# SCH_Sensor_Universal_PCB_w_XOR_2023-07-0.net
KiCad netlist of a schematic drawn in EasyEDA
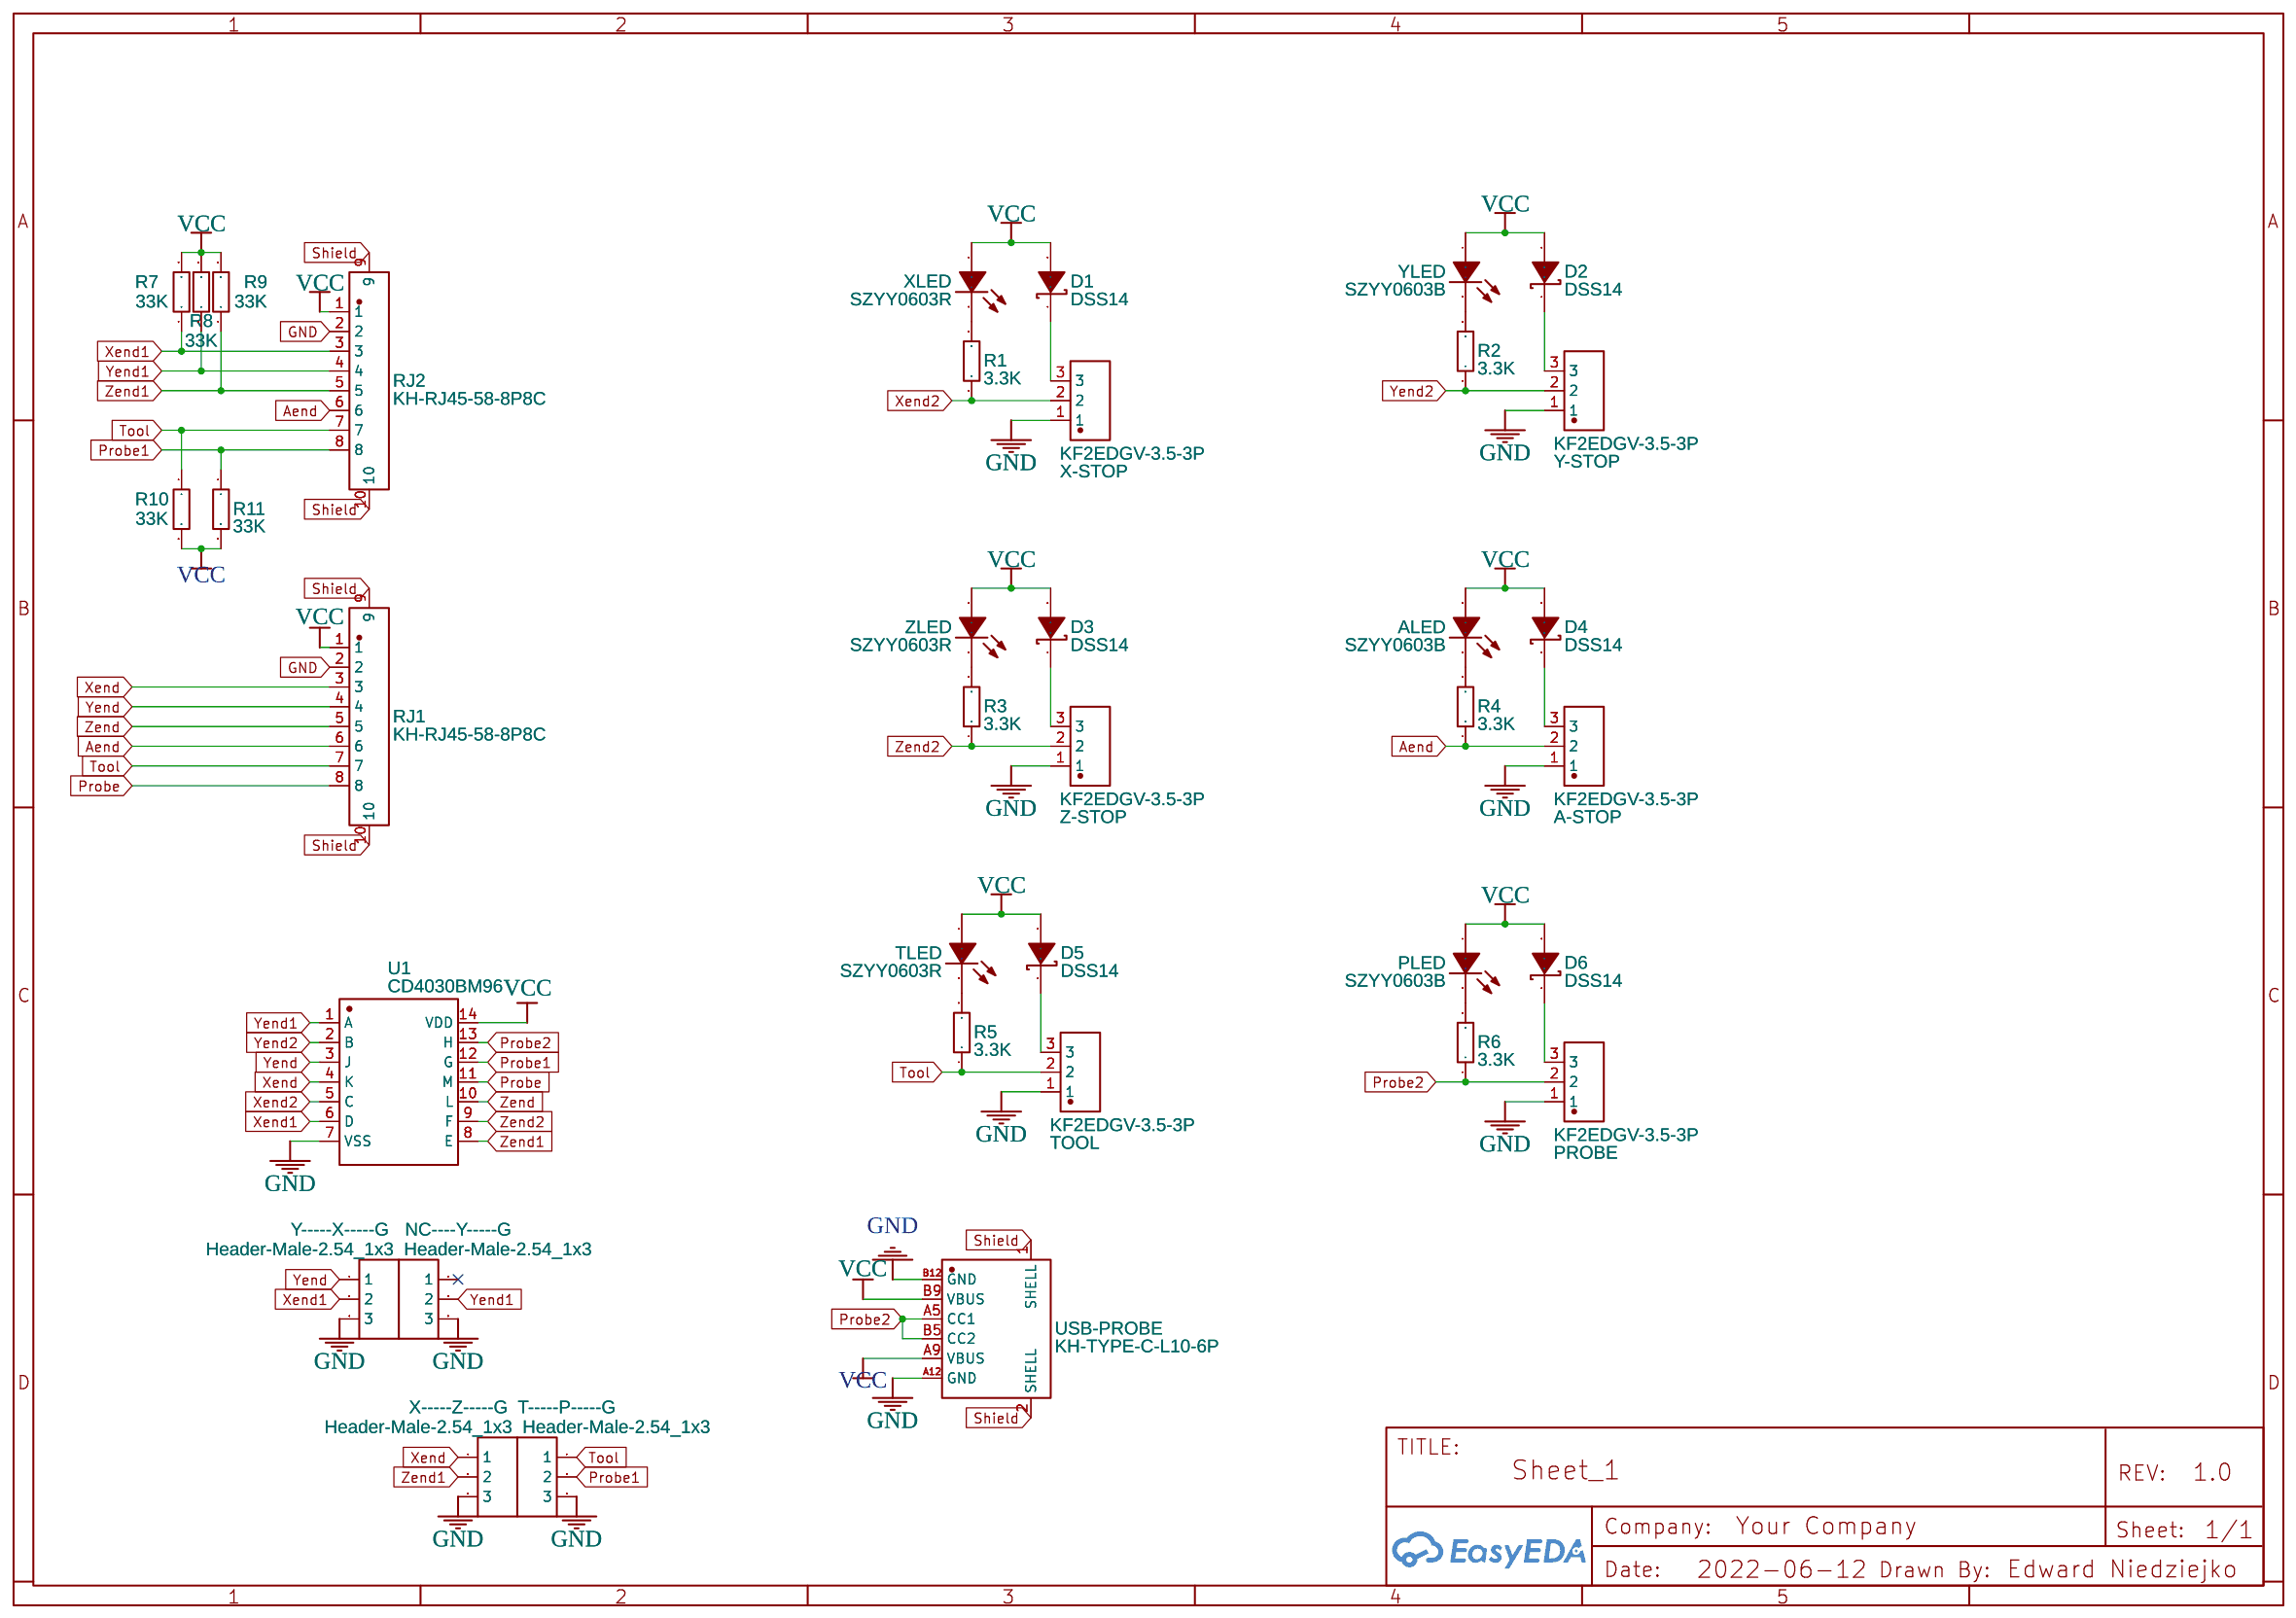
[diagram p0: schematic sheet]

(export (version "E")
  (design (tool "Eeschema 10.0.6"))
  (components
    (comp (ref "A-STOP")
      (value "KF2EDGV-3.5-3P")
      (fields (field (name "BOM_Supplier Part") "C441322"))
      (libsource (lib "") (part "KF2EDGV-3.5-3P_5"))
    )
    (comp (ref "ALED")
      (value "SZYY0603B")
      (fields (field (name "BOM_Supplier Part") "C434421"))
      (libsource (lib "") (part "SZYY0603B"))
    )
    (comp (ref "D1")
      (value "DSS14")
      (fields (field (name "BOM_Supplier Part") "C59293"))
      (libsource (lib "") (part "DSS14"))
    )
    (comp (ref "D2")
      (value "DSS14")
      (fields (field (name "BOM_Supplier Part") "C59293"))
      (libsource (lib "") (part "DSS14"))
    )
    (comp (ref "D3")
      (value "DSS14")
      (fields (field (name "BOM_Supplier Part") "C59293"))
      (libsource (lib "") (part "DSS14"))
    )
    (comp (ref "D4")
      (value "DSS14")
      (fields (field (name "BOM_Supplier Part") "C59293"))
      (libsource (lib "") (part "DSS14"))
    )
    (comp (ref "D5")
      (value "DSS14")
      (fields (field (name "BOM_Supplier Part") "C59293"))
      (libsource (lib "") (part "DSS14"))
    )
    (comp (ref "D6")
      (value "DSS14")
      (fields (field (name "BOM_Supplier Part") "C59293"))
      (libsource (lib "") (part "DSS14"))
    )
    (comp (ref "NC----Y-----G")
      (value "Header-Male-2.54_1x3")
      (fields (field (name "BOM_Manufacturer Part") "2.54-1*3P针") (field (name "BOM_Supplier Part") "C49257"))
      (libsource (lib "") (part "Header-Male-2.54_1x3_3"))
    )
    (comp (ref "PLED")
      (value "SZYY0603B")
      (fields (field (name "BOM_Supplier Part") "C434421"))
      (libsource (lib "") (part "SZYY0603B_1"))
    )
    (comp (ref "PROBE")
      (value "KF2EDGV-3.5-3P")
      (fields (field (name "BOM_Supplier Part") "C441322"))
      (libsource (lib "") (part "KF2EDGV-3.5-3P_2"))
    )
    (comp (ref "R1")
      (value "3.3K")
      (fields
        (field (name "BOM_Manufacturer Part") "RC0805FR-073K3L")
        (field (name "BOM_Supplier Part") "C114531")
      )
      (libsource (lib "") (part "RC0805FR-073K3L"))
    )
    (comp (ref "R2")
      (value "3.3K")
      (fields
        (field (name "BOM_Manufacturer Part") "RC0805FR-073K3L")
        (field (name "BOM_Supplier Part") "C114531")
      )
      (libsource (lib "") (part "RC0805FR-073K3L"))
    )
    (comp (ref "R3")
      (value "3.3K")
      (fields
        (field (name "BOM_Manufacturer Part") "RC0805FR-073K3L")
        (field (name "BOM_Supplier Part") "C114531")
      )
      (libsource (lib "") (part "RC0805FR-073K3L"))
    )
    (comp (ref "R4")
      (value "3.3K")
      (fields
        (field (name "BOM_Manufacturer Part") "RC0805FR-073K3L")
        (field (name "BOM_Supplier Part") "C114531")
      )
      (libsource (lib "") (part "RC0805FR-073K3L"))
    )
    (comp (ref "R5")
      (value "3.3K")
      (fields
        (field (name "BOM_Manufacturer Part") "RC0805FR-073K3L")
        (field (name "BOM_Supplier Part") "C114531")
      )
      (libsource (lib "") (part "RC0805FR-073K3L"))
    )
    (comp (ref "R6")
      (value "3.3K")
      (fields
        (field (name "BOM_Manufacturer Part") "RC0805FR-073K3L")
        (field (name "BOM_Supplier Part") "C114531")
      )
      (libsource (lib "") (part "RC0805FR-073K3L"))
    )
    (comp (ref "R7")
      (value "33K")
      (fields
        (field (name "BOM_Manufacturer Part") "RC0805JR-0733KL")
        (field (name "BOM_Supplier Part") "C137446")
      )
      (libsource (lib "") (part "RC0805JR-0733KL_1"))
    )
    (comp (ref "R8")
      (value "33K")
      (fields
        (field (name "BOM_Manufacturer Part") "RC0805JR-0733KL")
        (field (name "BOM_Supplier Part") "C137446")
      )
      (libsource (lib "") (part "RC0805JR-0733KL_1"))
    )
    (comp (ref "R9")
      (value "33K")
      (fields
        (field (name "BOM_Manufacturer Part") "RC0805JR-0733KL")
        (field (name "BOM_Supplier Part") "C137446")
      )
      (libsource (lib "") (part "RC0805JR-0733KL_1"))
    )
    (comp (ref "R10")
      (value "33K")
      (fields
        (field (name "BOM_Manufacturer Part") "RC0805JR-0733KL")
        (field (name "BOM_Supplier Part") "C137446")
      )
      (libsource (lib "") (part "RC0805JR-0733KL"))
    )
    (comp (ref "R11")
      (value "33K")
      (fields
        (field (name "BOM_Manufacturer Part") "RC0805JR-0733KL")
        (field (name "BOM_Supplier Part") "C137446")
      )
      (libsource (lib "") (part "RC0805JR-0733KL"))
    )
    (comp (ref "RJ1")
      (value "KH-RJ45-58-8P8C")
      (fields (field (name "BOM_Supplier Part") "C2683360"))
      (libsource (lib "") (part "KH-RJ45-58-8P8C"))
    )
    (comp (ref "RJ2")
      (value "KH-RJ45-58-8P8C")
      (fields (field (name "BOM_Supplier Part") "C2683360"))
      (libsource (lib "") (part "KH-RJ45-58-8P8C"))
    )
    (comp (ref "T-----P-----G")
      (value "Header-Male-2.54_1x3")
      (fields (field (name "BOM_Manufacturer Part") "2.54-1*3P针") (field (name "BOM_Supplier Part") "C49257"))
      (libsource (lib "") (part "Header-Male-2.54_1x3"))
    )
    (comp (ref "TLED")
      (value "SZYY0603R")
      (fields (field (name "BOM_Supplier Part") "C434419"))
      (libsource (lib "") (part "SZYY0603R"))
    )
    (comp (ref "TOOL")
      (value "KF2EDGV-3.5-3P")
      (fields (field (name "BOM_Supplier Part") "C441322"))
      (libsource (lib "") (part "KF2EDGV-3.5-3P"))
    )
    (comp (ref "U1")
      (value "CD4030BM96")
      (fields (field (name "BOM_Supplier Part") "C44237"))
      (libsource (lib "") (part "CD4030BM96"))
    )
    (comp (ref "USB-PROBE")
      (value "KH-TYPE-C-L10-6P")
      (fields (field (name "BOM_Supplier Part") "C2688788"))
      (libsource (lib "") (part "KH-TYPE-C-L10-6P"))
    )
    (comp (ref "X-----Z-----G")
      (value "Header-Male-2.54_1x3")
      (fields (field (name "BOM_Manufacturer Part") "2.54-1*3P针") (field (name "BOM_Supplier Part") "C49257"))
      (libsource (lib "") (part "Header-Male-2.54_1x3_2"))
    )
    (comp (ref "X-STOP")
      (value "KF2EDGV-3.5-3P")
      (fields (field (name "BOM_Supplier Part") "C441322"))
      (libsource (lib "") (part "KF2EDGV-3.5-3P_1"))
    )
    (comp (ref "XLED")
      (value "SZYY0603R")
      (fields (field (name "BOM_Supplier Part") "C434419"))
      (libsource (lib "") (part "SZYY0603R_1"))
    )
    (comp (ref "Y-----X-----G")
      (value "Header-Male-2.54_1x3")
      (fields (field (name "BOM_Manufacturer Part") "2.54-1*3P针") (field (name "BOM_Supplier Part") "C49257"))
      (libsource (lib "") (part "Header-Male-2.54_1x3_1"))
    )
    (comp (ref "Y-STOP")
      (value "KF2EDGV-3.5-3P")
      (fields (field (name "BOM_Supplier Part") "C441322"))
      (libsource (lib "") (part "KF2EDGV-3.5-3P_4"))
    )
    (comp (ref "YLED")
      (value "SZYY0603B")
      (fields (field (name "BOM_Supplier Part") "C434421"))
      (libsource (lib "") (part "SZYY0603B_2"))
    )
    (comp (ref "Z-STOP")
      (value "KF2EDGV-3.5-3P")
      (fields (field (name "BOM_Supplier Part") "C441322"))
      (libsource (lib "") (part "KF2EDGV-3.5-3P_3"))
    )
    (comp (ref "ZLED")
      (value "SZYY0603R")
      (fields (field (name "BOM_Supplier Part") "C434419"))
      (libsource (lib "") (part "SZYY0603R_2"))
    )
  )
  (nets
    (net (code "1") (name "Aend") (class "Default")
      (node (ref "A-STOP") (pin "2") (pinfunction "2_2") (pintype "unspecified"))
      (node (ref "R4") (pin "1") (pinfunction "1_1") (pintype "input"))
      (node (ref "RJ1") (pin "6") (pinfunction "6_6") (pintype "unspecified"))
      (node (ref "RJ2") (pin "6") (pinfunction "6_6") (pintype "unspecified"))
    )
    (net (code "2") (name "GND") (class "Default")
      (node (ref "A-STOP") (pin "1") (pinfunction "1_1") (pintype "unspecified"))
      (node (ref "NC----Y-----G") (pin "3") (pinfunction "3_3") (pintype "input"))
      (node (ref "PROBE") (pin "1") (pinfunction "1_1") (pintype "unspecified"))
      (node (ref "RJ1") (pin "2") (pinfunction "2_2") (pintype "unspecified"))
      (node (ref "RJ2") (pin "2") (pinfunction "2_2") (pintype "unspecified"))
      (node (ref "T-----P-----G") (pin "3") (pinfunction "3_3") (pintype "input"))
      (node (ref "TOOL") (pin "1") (pinfunction "1_1") (pintype "unspecified"))
      (node (ref "U1") (pin "7") (pinfunction "VSS_7") (pintype "unspecified"))
      (node (ref "USB-PROBE") (pin "A12") (pinfunction "GND_A12") (pintype "unspecified"))
      (node (ref "USB-PROBE") (pin "B12") (pinfunction "GND_B12") (pintype "unspecified"))
      (node (ref "X-----Z-----G") (pin "3") (pinfunction "3_3") (pintype "input"))
      (node (ref "X-STOP") (pin "1") (pinfunction "1_1") (pintype "unspecified"))
      (node (ref "Y-----X-----G") (pin "3") (pinfunction "3_3") (pintype "input"))
      (node (ref "Y-STOP") (pin "1") (pinfunction "1_1") (pintype "unspecified"))
      (node (ref "Z-STOP") (pin "1") (pinfunction "1_1") (pintype "unspecified"))
    )
    (net (code "3") (name "Net-(ALED--)") (class "Default")
      (node (ref "ALED") (pin "2") (pinfunction "-_2") (pintype "unspecified"))
      (node (ref "R4") (pin "2") (pinfunction "2_2") (pintype "input"))
    )
    (net (code "4") (name "Net-(D1-K)") (class "Default")
      (node (ref "D1") (pin "1") (pinfunction "K_1") (pintype "unspecified"))
      (node (ref "X-STOP") (pin "3") (pinfunction "3_3") (pintype "unspecified"))
    )
    (net (code "5") (name "Net-(D2-K)") (class "Default")
      (node (ref "D2") (pin "1") (pinfunction "K_1") (pintype "unspecified"))
      (node (ref "Y-STOP") (pin "3") (pinfunction "3_3") (pintype "unspecified"))
    )
    (net (code "6") (name "Net-(D3-K)") (class "Default")
      (node (ref "D3") (pin "1") (pinfunction "K_1") (pintype "unspecified"))
      (node (ref "Z-STOP") (pin "3") (pinfunction "3_3") (pintype "unspecified"))
    )
    (net (code "7") (name "Net-(D4-K)") (class "Default")
      (node (ref "A-STOP") (pin "3") (pinfunction "3_3") (pintype "unspecified"))
      (node (ref "D4") (pin "1") (pinfunction "K_1") (pintype "unspecified"))
    )
    (net (code "8") (name "Net-(D5-K)") (class "Default")
      (node (ref "D5") (pin "1") (pinfunction "K_1") (pintype "unspecified"))
      (node (ref "TOOL") (pin "3") (pinfunction "3_3") (pintype "unspecified"))
    )
    (net (code "9") (name "Net-(D6-K)") (class "Default")
      (node (ref "D6") (pin "1") (pinfunction "K_1") (pintype "unspecified"))
      (node (ref "PROBE") (pin "3") (pinfunction "3_3") (pintype "unspecified"))
    )
    (net (code "10") (name "Net-(PLED--)") (class "Default")
      (node (ref "PLED") (pin "2") (pinfunction "-_2") (pintype "unspecified"))
      (node (ref "R6") (pin "2") (pinfunction "2_2") (pintype "input"))
    )
    (net (code "11") (name "Net-(TLED--)") (class "Default")
      (node (ref "R5") (pin "2") (pinfunction "2_2") (pintype "input"))
      (node (ref "TLED") (pin "2") (pinfunction "-_2") (pintype "unspecified"))
    )
    (net (code "12") (name "Net-(XLED--)") (class "Default")
      (node (ref "R1") (pin "2") (pinfunction "2_2") (pintype "input"))
      (node (ref "XLED") (pin "2") (pinfunction "-_2") (pintype "unspecified"))
    )
    (net (code "13") (name "Net-(YLED--)") (class "Default")
      (node (ref "R2") (pin "2") (pinfunction "2_2") (pintype "input"))
      (node (ref "YLED") (pin "2") (pinfunction "-_2") (pintype "unspecified"))
    )
    (net (code "14") (name "Net-(ZLED--)") (class "Default")
      (node (ref "R3") (pin "2") (pinfunction "2_2") (pintype "input"))
      (node (ref "ZLED") (pin "2") (pinfunction "-_2") (pintype "unspecified"))
    )
    (net (code "15") (name "Probe") (class "Default")
      (node (ref "RJ1") (pin "8") (pinfunction "8_8") (pintype "unspecified"))
      (node (ref "U1") (pin "11") (pinfunction "M_11") (pintype "unspecified"))
    )
    (net (code "16") (name "Probe1") (class "Default")
      (node (ref "R11") (pin "1") (pinfunction "1_1") (pintype "input"))
      (node (ref "RJ2") (pin "8") (pinfunction "8_8") (pintype "unspecified"))
      (node (ref "T-----P-----G") (pin "2") (pinfunction "2_2") (pintype "input"))
      (node (ref "U1") (pin "12") (pinfunction "G_12") (pintype "unspecified"))
    )
    (net (code "17") (name "Probe2") (class "Default")
      (node (ref "PROBE") (pin "2") (pinfunction "2_2") (pintype "unspecified"))
      (node (ref "R6") (pin "1") (pinfunction "1_1") (pintype "input"))
      (node (ref "U1") (pin "13") (pinfunction "H_13") (pintype "unspecified"))
      (node (ref "USB-PROBE") (pin "A5") (pinfunction "CC1_A5") (pintype "unspecified"))
      (node (ref "USB-PROBE") (pin "B5") (pinfunction "CC2_B5") (pintype "unspecified"))
    )
    (net (code "18") (name "Shield") (class "Default")
      (node (ref "RJ1") (pin "10") (pinfunction "10_10") (pintype "unspecified"))
      (node (ref "RJ1") (pin "9") (pinfunction "9_9") (pintype "unspecified"))
      (node (ref "RJ2") (pin "10") (pinfunction "10_10") (pintype "unspecified"))
      (node (ref "RJ2") (pin "9") (pinfunction "9_9") (pintype "unspecified"))
      (node (ref "USB-PROBE") (pin "1") (pinfunction "SHELL_1") (pintype "unspecified"))
      (node (ref "USB-PROBE") (pin "2") (pinfunction "SHELL_2") (pintype "unspecified"))
    )
    (net (code "19") (name "Tool") (class "Default")
      (node (ref "R10") (pin "1") (pinfunction "1_1") (pintype "input"))
      (node (ref "R5") (pin "1") (pinfunction "1_1") (pintype "input"))
      (node (ref "RJ1") (pin "7") (pinfunction "7_7") (pintype "unspecified"))
      (node (ref "RJ2") (pin "7") (pinfunction "7_7") (pintype "unspecified"))
      (node (ref "T-----P-----G") (pin "1") (pinfunction "1_1") (pintype "input"))
      (node (ref "TOOL") (pin "2") (pinfunction "2_2") (pintype "unspecified"))
    )
    (net (code "20") (name "VCC") (class "Default")
      (node (ref "ALED") (pin "1") (pinfunction "+_1") (pintype "unspecified"))
      (node (ref "D1") (pin "2") (pinfunction "A_2") (pintype "unspecified"))
      (node (ref "D2") (pin "2") (pinfunction "A_2") (pintype "unspecified"))
      (node (ref "D3") (pin "2") (pinfunction "A_2") (pintype "unspecified"))
      (node (ref "D4") (pin "2") (pinfunction "A_2") (pintype "unspecified"))
      (node (ref "D5") (pin "2") (pinfunction "A_2") (pintype "unspecified"))
      (node (ref "D6") (pin "2") (pinfunction "A_2") (pintype "unspecified"))
      (node (ref "PLED") (pin "1") (pinfunction "+_1") (pintype "unspecified"))
      (node (ref "R10") (pin "2") (pinfunction "2_2") (pintype "input"))
      (node (ref "R11") (pin "2") (pinfunction "2_2") (pintype "input"))
      (node (ref "R7") (pin "2") (pinfunction "2_2") (pintype "input"))
      (node (ref "R8") (pin "2") (pinfunction "2_2") (pintype "input"))
      (node (ref "R9") (pin "2") (pinfunction "2_2") (pintype "input"))
      (node (ref "RJ1") (pin "1") (pinfunction "1_1") (pintype "unspecified"))
      (node (ref "RJ2") (pin "1") (pinfunction "1_1") (pintype "unspecified"))
      (node (ref "TLED") (pin "1") (pinfunction "+_1") (pintype "unspecified"))
      (node (ref "U1") (pin "14") (pinfunction "VDD_14") (pintype "unspecified"))
      (node (ref "USB-PROBE") (pin "A9") (pinfunction "VBUS_A9") (pintype "unspecified"))
      (node (ref "USB-PROBE") (pin "B9") (pinfunction "VBUS_B9") (pintype "unspecified"))
      (node (ref "XLED") (pin "1") (pinfunction "+_1") (pintype "unspecified"))
      (node (ref "YLED") (pin "1") (pinfunction "+_1") (pintype "unspecified"))
      (node (ref "ZLED") (pin "1") (pinfunction "+_1") (pintype "unspecified"))
    )
    (net (code "21") (name "Xend") (class "Default")
      (node (ref "RJ1") (pin "3") (pinfunction "3_3") (pintype "unspecified"))
      (node (ref "U1") (pin "4") (pinfunction "K_4") (pintype "unspecified"))
      (node (ref "X-----Z-----G") (pin "1") (pinfunction "1_1") (pintype "input"))
    )
    (net (code "22") (name "Xend1") (class "Default")
      (node (ref "R7") (pin "1") (pinfunction "1_1") (pintype "input"))
      (node (ref "RJ2") (pin "3") (pinfunction "3_3") (pintype "unspecified"))
      (node (ref "U1") (pin "6") (pinfunction "D_6") (pintype "unspecified"))
      (node (ref "Y-----X-----G") (pin "2") (pinfunction "2_2") (pintype "input"))
    )
    (net (code "23") (name "Xend2") (class "Default")
      (node (ref "R1") (pin "1") (pinfunction "1_1") (pintype "input"))
      (node (ref "U1") (pin "5") (pinfunction "C_5") (pintype "unspecified"))
      (node (ref "X-STOP") (pin "2") (pinfunction "2_2") (pintype "unspecified"))
    )
    (net (code "24") (name "Yend") (class "Default")
      (node (ref "RJ1") (pin "4") (pinfunction "4_4") (pintype "unspecified"))
      (node (ref "U1") (pin "3") (pinfunction "J_3") (pintype "unspecified"))
      (node (ref "Y-----X-----G") (pin "1") (pinfunction "1_1") (pintype "input"))
    )
    (net (code "25") (name "Yend1") (class "Default")
      (node (ref "NC----Y-----G") (pin "2") (pinfunction "2_2") (pintype "input"))
      (node (ref "R8") (pin "1") (pinfunction "1_1") (pintype "input"))
      (node (ref "RJ2") (pin "4") (pinfunction "4_4") (pintype "unspecified"))
      (node (ref "U1") (pin "1") (pinfunction "A_1") (pintype "unspecified"))
    )
    (net (code "26") (name "Yend2") (class "Default")
      (node (ref "R2") (pin "1") (pinfunction "1_1") (pintype "input"))
      (node (ref "U1") (pin "2") (pinfunction "B_2") (pintype "unspecified"))
      (node (ref "Y-STOP") (pin "2") (pinfunction "2_2") (pintype "unspecified"))
    )
    (net (code "27") (name "Zend") (class "Default")
      (node (ref "RJ1") (pin "5") (pinfunction "5_5") (pintype "unspecified"))
      (node (ref "U1") (pin "10") (pinfunction "L_10") (pintype "unspecified"))
    )
    (net (code "28") (name "Zend1") (class "Default")
      (node (ref "R9") (pin "1") (pinfunction "1_1") (pintype "input"))
      (node (ref "RJ2") (pin "5") (pinfunction "5_5") (pintype "unspecified"))
      (node (ref "U1") (pin "8") (pinfunction "E_8") (pintype "unspecified"))
      (node (ref "X-----Z-----G") (pin "2") (pinfunction "2_2") (pintype "input"))
    )
    (net (code "29") (name "Zend2") (class "Default")
      (node (ref "R3") (pin "1") (pinfunction "1_1") (pintype "input"))
      (node (ref "U1") (pin "9") (pinfunction "F_9") (pintype "unspecified"))
      (node (ref "Z-STOP") (pin "2") (pinfunction "2_2") (pintype "unspecified"))
    )
    (net (code "30") (name "unconnected-(NC----Y-----G-Pad1)") (class "Default")
      (node (ref "NC----Y-----G") (pin "1") (pinfunction "1_1") (pintype "input+no_connect"))
    )
  )
)
